# CHRT.net
KiCad netlist of a schematic drawn in Altium Designer
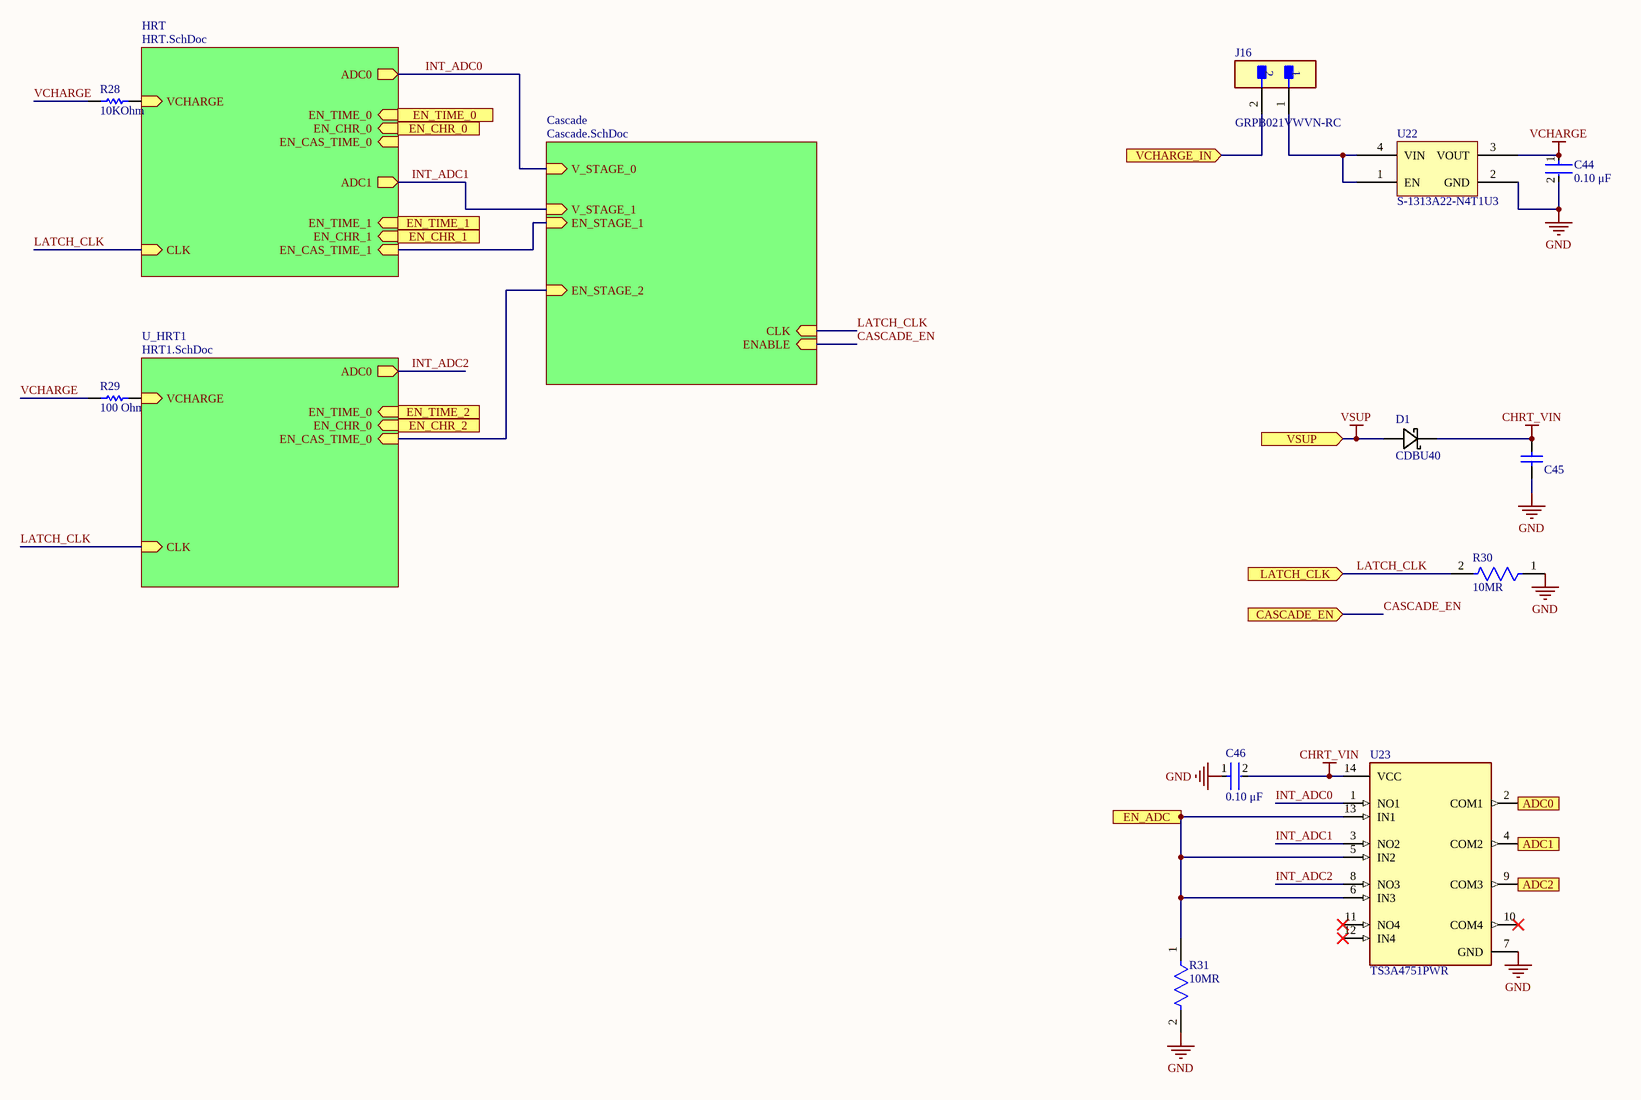
[diagram p0: CHRT.SchDoc]

(export (version "E")
  (design (tool "Eeschema 10.0.6"))
  (components
    (comp (ref "C44")
      (value "C0402C104K8PACTU")
      (footprint "FP-C0402-BB-MFG")
      (description "CAP CER 0.1UF 10V X5R 0402")
      (fields
        (field (name "CAPACITANCE") "0.10 μF")
        (field (name "MANUFACTURER") "Kemet")
        (field (name "TOLERANCE") "0.1")
      )
      (libsource (lib "Altium Content Vault") (part "b4654b650e69147ec39a6b967a45e02"))
    )
    (comp (ref "C45")
      (value "ZRB15XR61A106ME01D")
      (footprint "CAPC1005X55X25NL05T10")
      (fields (field (name "MANUFACTURER") "Murata") (field (name "PART NUMBER") "GRM155R60G106ME44D"))
      (libsource (lib "Altium Content Vault") (part "CAP"))
    )
    (comp (ref "C46")
      (value "C0402C104K8PACTU")
      (footprint "FP-C0402-BB-MFG")
      (description "CAP CER 0.1UF 10V X5R 0402")
      (fields
        (field (name "CAPACITANCE") "0.10 μF")
        (field (name "MANUFACTURER") "Kemet")
        (field (name "TOLERANCE") "0.1")
      )
      (libsource (lib "Altium Content Vault") (part "b4654b650e69147ec39a6b967a45e02"))
    )
    (comp (ref "D1")
      (value "CDBU40")
      (footprint "CDBU")
      (description "No Description Available")
      (fields (field (name "COPYRIGHT") "Copyright (C) 2022 Ultra Librarian. All rights reserved."))
      (libsource (lib "CDBU40") (part "CDBU40"))
    )
    (comp (ref "J16")
      (value "GRPB021VWVN-RC")
      (footprint "FP-GRPB021VWVN-RC-MFG")
      (description "CONN HEADER VERT 2POS 1.27MM")
      (libsource (lib "Altium Content Vault") (part "3bc925449376181038e59eaffc5286c"))
    )
    (comp (ref "R28")
      (value "RMCF0402FT10K0")
      (footprint "RESC1005X40X25LL05T05")
      (description "Chip Resistor, 10 KOhm, +/- 1%, 0.1 W, -55 to 155 degC, 0402 (1005 Metric), RoHS, Tape and Reel")
      (fields
        (field (name "RESISTANCE") "10KOhm")
        (field (name "TOLERANCE") "1%")
        (field (name "MANUFACTURER") "Panasonic")
      )
      (libsource (lib "Altium Content Vault") (part "RES-2"))
    )
    (comp (ref "R29")
      (value "ERJ-2RKF1000X")
      (footprint "RESC1005X40X25LL05T05")
      (description "Chip Resistor, 100 Ohm, +/- 1%, 100 mW, -55 to 155 degC, 0402 (1005 Metric), RoHS, Tape and Reel")
      (fields
        (field (name "MANUFACTURER") "Basic Passives")
        (field (name "TOLERANCE") "1%")
        (field (name "RESISTANCE") "100 Ohm")
      )
      (libsource (lib "Altium Content Vault") (part "RES-2"))
    )
    (comp (ref "R30")
      (value "CRCW040210M0JNED")
      (footprint "FP-CRCW0402-e3-IPC_C")
      (description "RES Thick Film, 10MΩ, 5%, 0.063W, 200ppm/°C, 0402")
      (fields (field (name "TOLERANCE") "5%") (field (name "RESISTANCE") "10MR"))
      (libsource (lib "Altium Content Vault") (part "1029c3af85768c4190bb7ad29bc67b5"))
    )
    (comp (ref "R31")
      (value "CRCW040210M0JNED")
      (footprint "FP-CRCW0402-e3-IPC_C")
      (description "RES Thick Film, 10MΩ, 5%, 0.063W, 200ppm/°C, 0402")
      (fields (field (name "TOLERANCE") "5%") (field (name "RESISTANCE") "10MR"))
      (libsource (lib "Altium Content Vault") (part "1029c3af85768c4190bb7ad29bc67b5"))
    )
    (comp (ref "U22")
      (value "S-1313A22-N4T1U3")
      (footprint "SOT130P210X110-4N")
      (libsource (lib "Integrated_Library1") (part "S-1313A22-N4T1U3"))
    )
    (comp (ref "U23")
      (value "TS3A4751PWR")
      (footprint "FP-PW0014A-IPC_C")
      (description "IC SWITCH QUAD SPST 14TSSOP")
      (libsource (lib "Altium Content Vault") (part "75fdcfb842d41a92b92a478e82e68ae"))
    )
  )
  (nets
    (net (code "1") (name "/ADC0") (class "Default")
      (node (ref "U23") (pin "2") (pinfunction "COM1_2") (pintype "output"))
    )
    (net (code "2") (name "/ADC1") (class "Default")
      (node (ref "U23") (pin "4") (pinfunction "COM2_4") (pintype "output"))
    )
    (net (code "3") (name "/ADC2") (class "Default")
      (node (ref "U23") (pin "9") (pinfunction "COM3_9") (pintype "output"))
    )
    (net (code "5") (name "/EN_ADC") (class "Default")
      (node (ref "R31") (pin "1") (pinfunction "1_1") (pintype "passive"))
      (node (ref "U23") (pin "13") (pinfunction "IN1_13") (pintype "input"))
      (node (ref "U23") (pin "5") (pinfunction "IN2_5") (pintype "input"))
      (node (ref "U23") (pin "6") (pinfunction "IN3_6") (pintype "input"))
    )
    (net (code "15") (name "/INT_ADC0") (class "Default")
      (node (ref "U23") (pin "1") (pinfunction "NO1_1") (pintype "input"))
    )
    (net (code "16") (name "/INT_ADC1") (class "Default")
      (node (ref "U23") (pin "3") (pinfunction "NO2_3") (pintype "input"))
    )
    (net (code "17") (name "/INT_ADC2") (class "Default")
      (node (ref "U23") (pin "8") (pinfunction "NO3_8") (pintype "input"))
    )
    (net (code "18") (name "/LATCH_CLK") (class "Default")
      (node (ref "R30") (pin "2") (pinfunction "2_2") (pintype "passive"))
    )
    (net (code "19") (name "/VCHARGE_1") (class "Default")
      (node (ref "R29") (pin "2") (pinfunction "2_2") (pintype "passive"))
    )
    (net (code "20") (name "/VCHARGE_2") (class "Default")
      (node (ref "R28") (pin "2") (pinfunction "2_2") (pintype "passive"))
    )
    (net (code "21") (name "/VCHARGE_IN") (class "Default")
      (node (ref "J16") (pin "2") (pinfunction "2_2") (pintype "passive"))
    )
    (net (code "22") (name "CHRT_VIN") (class "Default")
      (node (ref "C45") (pin "2") (pinfunction "2_2") (pintype "passive"))
      (node (ref "C46") (pin "2") (pinfunction "2_2") (pintype "passive"))
      (node (ref "D1") (pin "1") (pinfunction "1_1") (pintype "passive"))
      (node (ref "U23") (pin "14") (pinfunction "VCC_14") (pintype "power_in"))
    )
    (net (code "23") (name "GND") (class "Default")
      (node (ref "C44") (pin "2") (pinfunction "2_2") (pintype "passive"))
      (node (ref "C45") (pin "1") (pinfunction "1_1") (pintype "passive"))
      (node (ref "C46") (pin "1") (pinfunction "1_1") (pintype "passive"))
      (node (ref "R30") (pin "1") (pinfunction "1_1") (pintype "passive"))
      (node (ref "R31") (pin "2") (pinfunction "2_2") (pintype "passive"))
      (node (ref "U22") (pin "2") (pinfunction "GND_2") (pintype "passive"))
      (node (ref "U23") (pin "7") (pinfunction "GND_7") (pintype "power_in"))
    )
    (net (code "24") (name "Net-(U22-EN)") (class "Default")
      (node (ref "J16") (pin "1") (pinfunction "1_1") (pintype "passive"))
      (node (ref "U22") (pin "1") (pinfunction "EN_1") (pintype "passive"))
      (node (ref "U22") (pin "4") (pinfunction "VIN_4") (pintype "passive"))
    )
    (net (code "25") (name "VCHARGE") (class "Default")
      (node (ref "C44") (pin "1") (pinfunction "1_1") (pintype "passive"))
      (node (ref "R28") (pin "1") (pinfunction "1_1") (pintype "passive"))
      (node (ref "R29") (pin "1") (pinfunction "1_1") (pintype "passive"))
      (node (ref "U22") (pin "3") (pinfunction "VOUT_3") (pintype "passive"))
    )
    (net (code "26") (name "VSUP") (class "Default")
      (node (ref "D1") (pin "2") (pinfunction "2_2") (pintype "passive"))
    )
    (net (code "27") (name "unconnected-(U23-COM4-Pad10)") (class "Default")
      (node (ref "U23") (pin "10") (pinfunction "COM4_10") (pintype "output+no_connect"))
    )
    (net (code "28") (name "unconnected-(U23-IN4-Pad12)") (class "Default")
      (node (ref "U23") (pin "12") (pinfunction "IN4_12") (pintype "input+no_connect"))
    )
    (net (code "29") (name "unconnected-(U23-NO4-Pad11)") (class "Default")
      (node (ref "U23") (pin "11") (pinfunction "NO4_11") (pintype "input+no_connect"))
    )
  )
)
